# power.net
KiCad netlist of a schematic drawn in Altium Designer
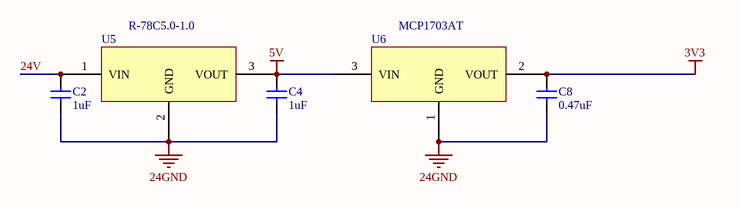
[diagram p0: power.SchDoc]

(export (version "E")
  (design (tool "Eeschema 10.0.6"))
  (components
    (comp (ref "C2")
      (value "1uF")
      (footprint "CAPC1206")
      (fields (field (name "Comment") "Cap"))
      (libsource (lib "SubjuGator8") (part "Cap"))
    )
    (comp (ref "C4")
      (value "1uF")
      (footprint "CAPC1206")
      (fields (field (name "Comment") "Cap"))
      (libsource (lib "SubjuGator8") (part "Cap"))
    )
    (comp (ref "C8")
      (value "0.47uF")
      (footprint "CAPC0603")
      (fields (field (name "Comment") "Cap"))
      (libsource (lib "SubjuGator8") (part "Cap"))
    )
    (comp (ref "U5")
      (value "R-78C5.0-1.0")
      (footprint "R-78C5.0-1.0")
      (description "CONV DC/DC 1A 5V OUT SIP VERT")
      (libsource (lib "SubjuGator8") (part "R-78C5.0-1.0"))
    )
    (comp (ref "U6")
      (value "MCP1703AT")
      (footprint "MCP1703AT-xx02EDB")
      (description "250 mA, 16V, Low Quiescent Current LDO Regulator")
      (libsource (lib "SubjuGator8") (part "MCP1703AT"))
    )
  )
  (nets
    (net (code "1") (name "/24V") (class "Default")
      (node (ref "C2") (pin "1") (pinfunction "A_1") (pintype "passive"))
      (node (ref "U5") (pin "1") (pinfunction "VIN_1") (pintype "passive"))
    )
    (net (code "2") (name "3V3") (class "Default")
      (node (ref "C8") (pin "1") (pinfunction "A_1") (pintype "passive"))
      (node (ref "U6") (pin "2") (pinfunction "VOUT_2") (pintype "passive"))
    )
    (net (code "3") (name "5V") (class "Default")
      (node (ref "C4") (pin "1") (pinfunction "A_1") (pintype "passive"))
      (node (ref "U5") (pin "3") (pinfunction "VOUT_3") (pintype "passive"))
      (node (ref "U6") (pin "3") (pinfunction "VIN_3") (pintype "passive"))
    )
    (net (code "4") (name "24GND") (class "Default")
      (node (ref "C2") (pin "2") (pinfunction "B_2") (pintype "passive"))
      (node (ref "C4") (pin "2") (pinfunction "B_2") (pintype "passive"))
      (node (ref "C8") (pin "2") (pinfunction "B_2") (pintype "passive"))
      (node (ref "U5") (pin "2") (pinfunction "GND_2") (pintype "power_in"))
      (node (ref "U6") (pin "1") (pinfunction "GND_1") (pintype "power_in"))
    )
  )
)
